# alim_sym.net
KiCad netlist of a schematic drawn in EAGLE
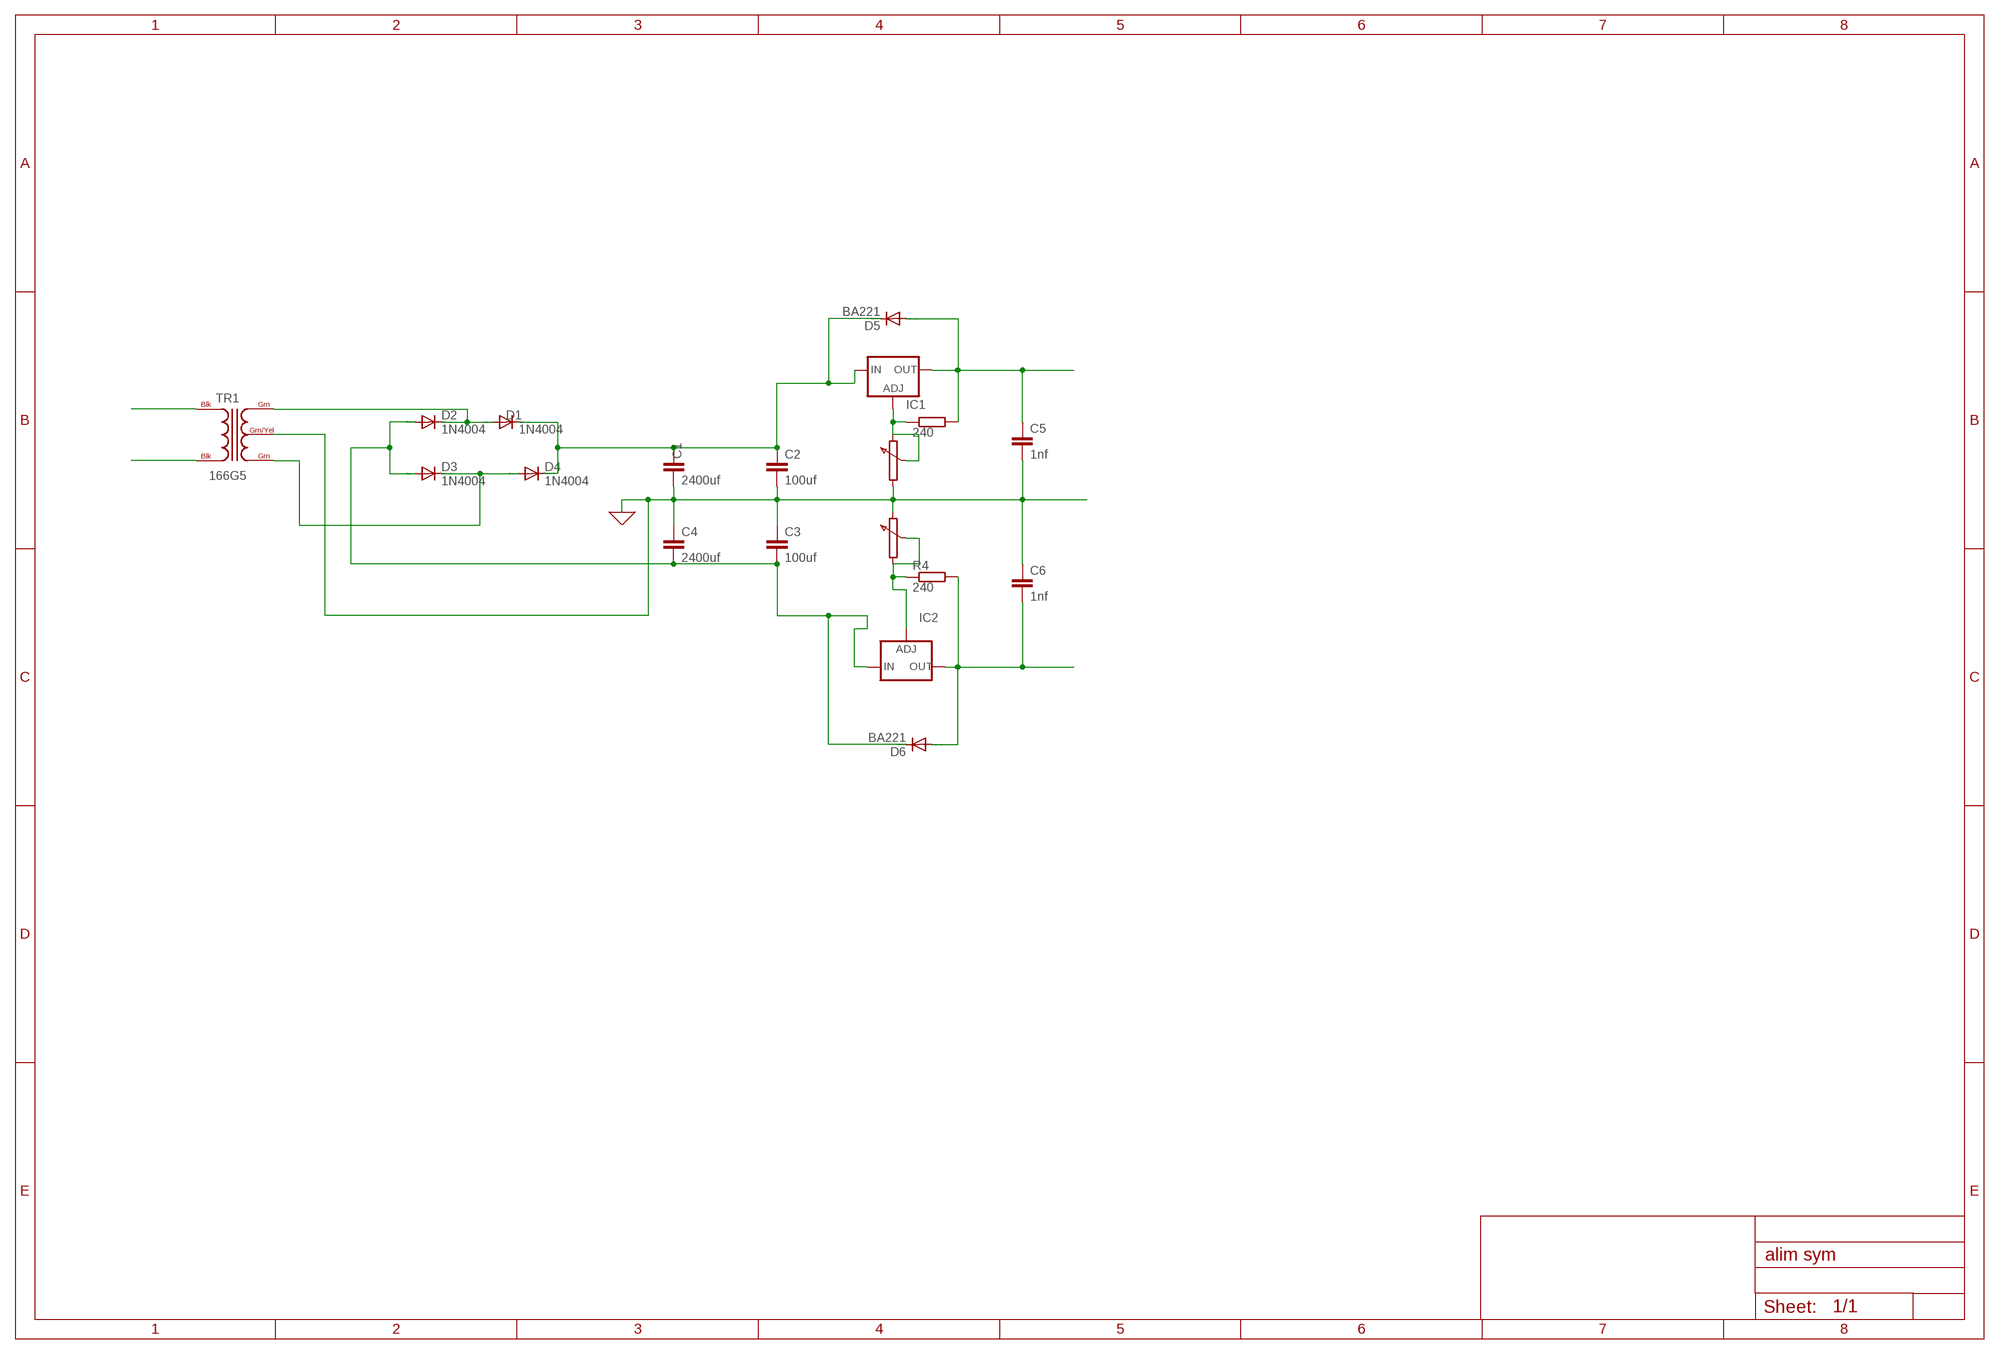
[diagram p0: schematic, sheet 1]

(export (version "E")
  (design (tool "Eeschema 10.0.6"))
  (components
    (comp (ref "C1")
      (value "2400uf")
      (footprint "eagle-import:C2.5-3")
      (libsource (lib "eagle-import") (part "C2,5-3"))
    )
    (comp (ref "C2")
      (value "100uf")
      (footprint "eagle-import:C2.5-3")
      (libsource (lib "eagle-import") (part "C2,5-3"))
    )
    (comp (ref "C3")
      (value "100uf")
      (footprint "eagle-import:C2.5-3")
      (libsource (lib "eagle-import") (part "C2,5-3"))
    )
    (comp (ref "C4")
      (value "2400uf")
      (footprint "eagle-import:C2.5-3")
      (libsource (lib "eagle-import") (part "C2,5-3"))
    )
    (comp (ref "C5")
      (value "1nf")
      (footprint "eagle-import:C2.5-3")
      (libsource (lib "eagle-import") (part "C2,5-3"))
    )
    (comp (ref "C6")
      (value "1nf")
      (footprint "eagle-import:C2.5-3")
      (libsource (lib "eagle-import") (part "C2,5-3"))
    )
    (comp (ref "D1")
      (value "1N4004")
      (footprint "eagle-import:DO41-10")
      (libsource (lib "eagle-import") (part "1N4004"))
    )
    (comp (ref "D2")
      (value "1N4004")
      (footprint "eagle-import:DO41-10")
      (libsource (lib "eagle-import") (part "1N4004"))
    )
    (comp (ref "D3")
      (value "1N4004")
      (footprint "eagle-import:DO41-10")
      (libsource (lib "eagle-import") (part "1N4004"))
    )
    (comp (ref "D4")
      (value "1N4004")
      (footprint "eagle-import:DO41-10")
      (libsource (lib "eagle-import") (part "1N4004"))
    )
    (comp (ref "D5")
      (value "BA221")
      (footprint "eagle-import:DO35-10")
      (libsource (lib "eagle-import") (part "BA221"))
    )
    (comp (ref "D6")
      (value "BA221")
      (footprint "eagle-import:DO35-10")
      (libsource (lib "eagle-import") (part "BA221"))
    )
    (comp (ref "IC1")
      (value "LM317TS")
      (footprint "eagle-import:317TS")
      (libsource (lib "eagle-import") (part "LM317TS"))
    )
    (comp (ref "IC2")
      (value "LM337TS")
      (footprint "eagle-import:337TS")
      (libsource (lib "eagle-import") (part "LM337TS"))
    )
    (comp (ref "R3")
      (value "240")
      (footprint "eagle-import:SMS-0")
      (libsource (lib "eagle-import") (part "SMS-0"))
    )
    (comp (ref "R4")
      (value "240")
      (footprint "eagle-import:SMS-0")
      (libsource (lib "eagle-import") (part "SMS-0"))
    )
    (comp (ref "TR1")
      (value "166G5")
      (footprint "eagle-import:C3H")
      (libsource (lib "eagle-import") (part "166G5"))
    )
  )
  (nets
    (net (code "1") (name "GND") (class "Default")
      (node (ref "C1") (pin "2") (pinfunction "2_2") (pintype "passive"))
      (node (ref "C2") (pin "2") (pinfunction "2_2") (pintype "passive"))
      (node (ref "C3") (pin "1") (pinfunction "1_1") (pintype "passive"))
      (node (ref "C4") (pin "1") (pinfunction "1_1") (pintype "passive"))
      (node (ref "C5") (pin "2") (pinfunction "2_2") (pintype "passive"))
      (node (ref "C6") (pin "1") (pinfunction "1_1") (pintype "passive"))
      (node (ref "TR1") (pin "GRN/YEL") (pinfunction "GRN/YEL_GRN/YEL") (pintype "passive"))
    )
    (net (code "2") (name "Net-(D1-PadA)") (class "Default")
      (node (ref "D1") (pin "A") (pinfunction "A_A") (pintype "passive"))
      (node (ref "D2") (pin "C") (pinfunction "C_C") (pintype "passive"))
      (node (ref "TR1") (pin "GRN@1") (pinfunction "GRN_GRN@1") (pintype "passive"))
    )
    (net (code "3") (name "Net-(D3-PadC)") (class "Default")
      (node (ref "D3") (pin "C") (pinfunction "C_C") (pintype "passive"))
      (node (ref "D4") (pin "A") (pinfunction "A_A") (pintype "passive"))
      (node (ref "TR1") (pin "GRN@2") (pinfunction "GRN_GRN@2") (pintype "passive"))
    )
    (net (code "4") (name "Net-(IC1-ADJ)") (class "Default")
      (node (ref "IC1") (pin "1") (pinfunction "ADJ_1") (pintype "input"))
      (node (ref "R3") (pin "2") (pinfunction "2_2") (pintype "passive"))
    )
    (net (code "5") (name "Net-(IC1-IN)") (class "Default")
      (node (ref "C1") (pin "1") (pinfunction "1_1") (pintype "passive"))
      (node (ref "C2") (pin "1") (pinfunction "1_1") (pintype "passive"))
      (node (ref "D1") (pin "C") (pinfunction "C_C") (pintype "passive"))
      (node (ref "D4") (pin "C") (pinfunction "C_C") (pintype "passive"))
      (node (ref "D5") (pin "C") (pinfunction "C_C") (pintype "passive"))
      (node (ref "IC1") (pin "3") (pinfunction "IN_3") (pintype "input"))
    )
    (net (code "6") (name "Net-(IC1-OUT)") (class "Default")
      (node (ref "C5") (pin "1") (pinfunction "1_1") (pintype "passive"))
      (node (ref "D5") (pin "A") (pinfunction "A_A") (pintype "passive"))
      (node (ref "IC1") (pin "2") (pinfunction "OUT_2") (pintype "passive"))
      (node (ref "R3") (pin "1") (pinfunction "1_1") (pintype "passive"))
    )
    (net (code "7") (name "Net-(IC2-ADJ)") (class "Default")
      (node (ref "IC2") (pin "1") (pinfunction "ADJ_1") (pintype "input"))
      (node (ref "R4") (pin "2") (pinfunction "2_2") (pintype "passive"))
    )
    (net (code "8") (name "Net-(IC2-IN)") (class "Default")
      (node (ref "C3") (pin "2") (pinfunction "2_2") (pintype "passive"))
      (node (ref "C4") (pin "2") (pinfunction "2_2") (pintype "passive"))
      (node (ref "D2") (pin "A") (pinfunction "A_A") (pintype "passive"))
      (node (ref "D3") (pin "A") (pinfunction "A_A") (pintype "passive"))
      (node (ref "D6") (pin "C") (pinfunction "C_C") (pintype "passive"))
      (node (ref "IC2") (pin "2") (pinfunction "IN_2") (pintype "input"))
    )
    (net (code "9") (name "Net-(IC2-OUT)") (class "Default")
      (node (ref "C6") (pin "2") (pinfunction "2_2") (pintype "passive"))
      (node (ref "D6") (pin "A") (pinfunction "A_A") (pintype "passive"))
      (node (ref "IC2") (pin "3") (pinfunction "OUT_3") (pintype "passive"))
      (node (ref "R4") (pin "1") (pinfunction "1_1") (pintype "passive"))
    )
    (net (code "10") (name "unconnected-(TR1-BLK-PadBLK@1)") (class "Default")
      (node (ref "TR1") (pin "BLK@1") (pinfunction "BLK_BLK@1") (pintype "passive"))
    )
    (net (code "11") (name "unconnected-(TR1-BLK-PadBLK@2)") (class "Default")
      (node (ref "TR1") (pin "BLK@2") (pinfunction "BLK_BLK@2") (pintype "passive"))
    )
  )
)
